# Ultra-Mega-PS-Block-V1_00.net
KiCad netlist of a schematic drawn in Altium Designer
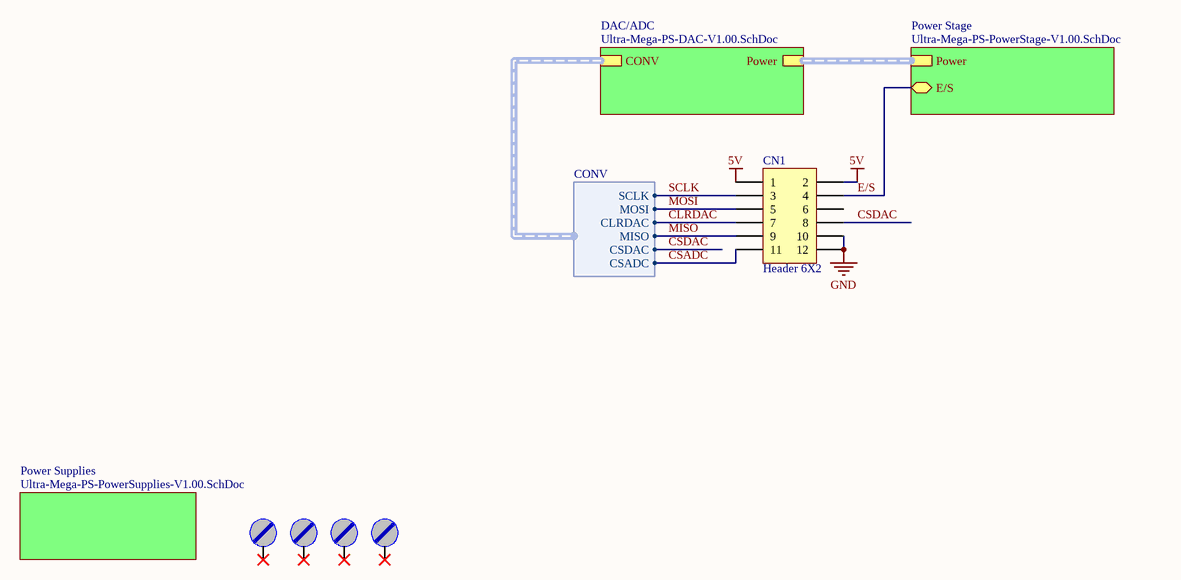
[diagram p0: Ultra-Mega-PS-Block-V1.00.SchDoc]

(export (version "E")
  (design (tool "Eeschema 10.0.6"))
  (components
    (comp (ref "CN1")
      (value "Header 6X2")
      (footprint "CONN HDR2X6")
      (description "Header, 6-Pin, Dual row")
      (libsource (lib "NavarroCON") (part "Header 6X2"))
    )
    (comp (ref "HOLE1")
      (value "Furo de Fixação")
      (footprint "Furo_M3")
      (description "Furo para parafuso")
      (libsource (lib "Navarro") (part "Parafuso"))
    )
    (comp (ref "HOLE2")
      (value "Furo de Fixação")
      (footprint "Furo_M3")
      (description "Furo para parafuso")
      (libsource (lib "Navarro") (part "Parafuso"))
    )
    (comp (ref "HOLE3")
      (value "Furo de Fixação")
      (footprint "Furo_M3")
      (description "Furo para parafuso")
      (libsource (lib "Navarro") (part "Parafuso"))
    )
    (comp (ref "HOLE4")
      (value "Furo de Fixação")
      (footprint "Furo_M3")
      (description "Furo para parafuso")
      (libsource (lib "Navarro") (part "Parafuso"))
    )
  )
  (nets
    (net (code "2") (name "/CLRDAC") (class "Default")
      (node (ref "CN1") (pin "7") (pinfunction "7_7") (pintype "passive"))
    )
    (net (code "3") (name "/CSADC") (class "Default")
      (node (ref "CN1") (pin "11") (pinfunction "11_11") (pintype "passive"))
    )
    (net (code "4") (name "/CSDAC") (class "Default")
      (node (ref "CN1") (pin "8") (pinfunction "8_8") (pintype "passive"))
    )
    (net (code "5") (name "/E{slash}S") (class "Default")
      (node (ref "CN1") (pin "4") (pinfunction "4_4") (pintype "passive"))
    )
    (net (code "6") (name "/MISO") (class "Default")
      (node (ref "CN1") (pin "9") (pinfunction "9_9") (pintype "passive"))
    )
    (net (code "7") (name "/MOSI") (class "Default")
      (node (ref "CN1") (pin "5") (pinfunction "5_5") (pintype "passive"))
    )
    (net (code "9") (name "/SCLK") (class "Default")
      (node (ref "CN1") (pin "3") (pinfunction "3_3") (pintype "passive"))
    )
    (net (code "11") (name "5V") (class "Default")
      (node (ref "CN1") (pin "1") (pinfunction "1_1") (pintype "passive"))
      (node (ref "CN1") (pin "2") (pinfunction "2_2") (pintype "passive"))
    )
    (net (code "12") (name "GND") (class "Default")
      (node (ref "CN1") (pin "10") (pinfunction "10_10") (pintype "passive"))
      (node (ref "CN1") (pin "12") (pinfunction "12_12") (pintype "passive"))
    )
    (net (code "13") (name "unconnected-(CN1-Pad6)") (class "Default")
      (node (ref "CN1") (pin "6") (pinfunction "6_6") (pintype "passive"))
    )
    (net (code "14") (name "unconnected-(HOLE1-PadX)") (class "Default")
      (node (ref "HOLE1") (pin "X") (pinfunction "X_X") (pintype "passive+no_connect"))
    )
    (net (code "15") (name "unconnected-(HOLE2-PadX)") (class "Default")
      (node (ref "HOLE2") (pin "X") (pinfunction "X_X") (pintype "passive+no_connect"))
    )
    (net (code "16") (name "unconnected-(HOLE3-PadX)") (class "Default")
      (node (ref "HOLE3") (pin "X") (pinfunction "X_X") (pintype "passive+no_connect"))
    )
    (net (code "17") (name "unconnected-(HOLE4-PadX)") (class "Default")
      (node (ref "HOLE4") (pin "X") (pinfunction "X_X") (pintype "passive+no_connect"))
    )
  )
)
